# MCU.net
KiCad netlist of a schematic drawn in Altium Designer
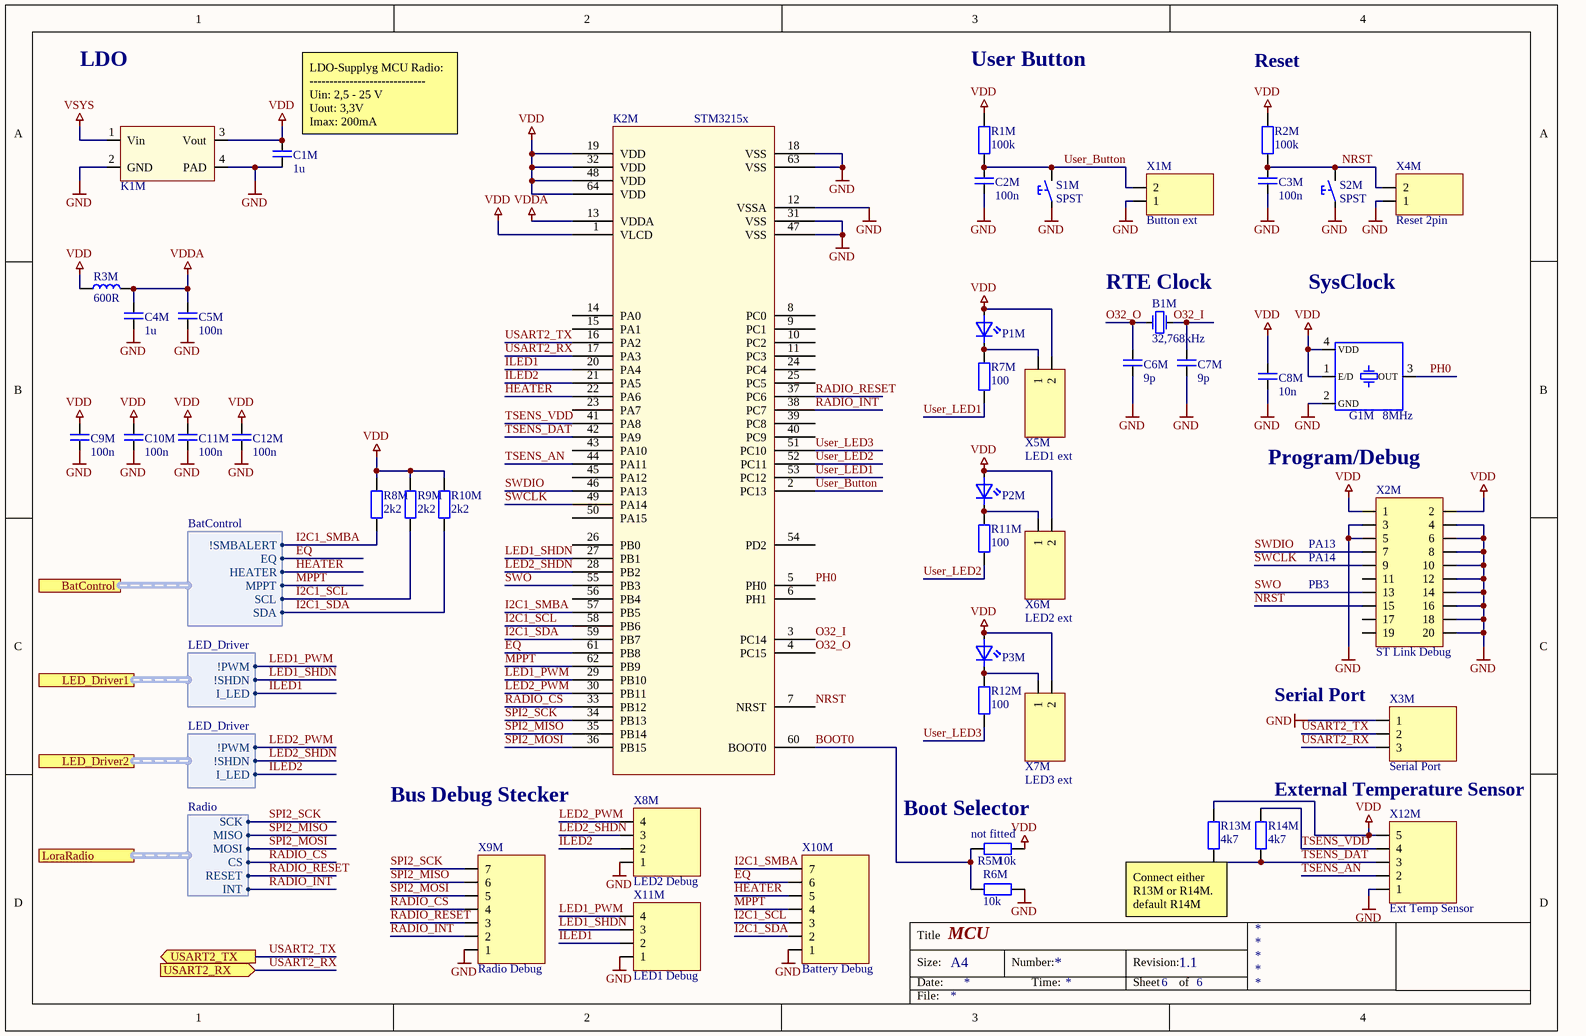
[diagram p0: MCU.SchDoc]

(export (version "E")
  (design (tool "Eeschema 10.0.6"))
  (components
    (comp (ref "B1M")
      (value "32,768kHz")
      (footprint "0805")
      (libsource (lib "Elektromechanical") (part "Quarz"))
    )
    (comp (ref "C1M") (value "1u") (footprint "0805") (libsource (lib "Passive") (part "Kondensator")))
    (comp (ref "C2M") (value "100n") (footprint "0805") (libsource (lib "Passive") (part "Kondensator")))
    (comp (ref "C3M") (value "100n") (footprint "0805") (libsource (lib "Passive") (part "Kondensator")))
    (comp (ref "C4M") (value "1u") (footprint "0805") (libsource (lib "Passive") (part "Kondensator")))
    (comp (ref "C5M") (value "100n") (footprint "0805") (libsource (lib "Passive") (part "Kondensator")))
    (comp (ref "C6M") (value "9p") (footprint "0805") (libsource (lib "Passive") (part "Kondensator")))
    (comp (ref "C7M") (value "9p") (footprint "0805") (libsource (lib "Passive") (part "Kondensator")))
    (comp (ref "C8M") (value "10n") (footprint "0805") (libsource (lib "Passive") (part "Kondensator")))
    (comp (ref "C9M") (value "100n") (footprint "0805") (libsource (lib "Passive") (part "Kondensator")))
    (comp (ref "C10M") (value "100n") (footprint "0805") (libsource (lib "Passive") (part "Kondensator")))
    (comp (ref "C11M") (value "100n") (footprint "0805") (libsource (lib "Passive") (part "Kondensator")))
    (comp (ref "C12M") (value "100n") (footprint "0805") (libsource (lib "Passive") (part "Kondensator")))
    (comp (ref "G1M")
      (value "8MHz")
      (footprint "SMT 3.2x2.5")
      (libsource (lib "Electromechanical") (part "Quarz Oszillator"))
    )
    (comp (ref "K1M") (value "LDO_2") (footprint "SOT223-4L") (libsource (lib "IC") (part "LDO_2")))
    (comp (ref "K2M")
      (value "STM3215x")
      (footprint "LQFP64, 0.5mm pitch")
      (libsource (lib "MCU") (part "STM32L15xRE_64"))
    )
    (comp (ref "P1M")
      (value "LED grün")
      (footprint "1206 D")
      (libsource (lib "Optoelectronics") (part "LED"))
    )
    (comp (ref "P2M")
      (value "LED gelb")
      (footprint "1206 D")
      (libsource (lib "Optoelectronics") (part "LED"))
    )
    (comp (ref "P3M") (value "LED rot") (footprint "1206 D") (libsource (lib "Optoelectronics") (part "LED")))
    (comp (ref "R1M") (value "100k") (footprint "0805") (libsource (lib "Passive") (part "Widerstand")))
    (comp (ref "R2M") (value "100k") (footprint "0805") (libsource (lib "Passive") (part "Widerstand")))
    (comp (ref "R3M")
      (value "600R")
      (footprint "0805")
      (description "EMI Filter")
      (libsource (lib "Passive") (part "Induktivität"))
    )
    (comp (ref "R5M") (value "10k") (footprint "0805") (libsource (lib "Passive") (part "Widerstand")))
    (comp (ref "R6M") (value "10k") (footprint "0805") (libsource (lib "Passive") (part "Widerstand")))
    (comp (ref "R7M") (value "100") (footprint "0805") (libsource (lib "Passive") (part "Widerstand")))
    (comp (ref "R8M") (value "2k2") (footprint "0805") (libsource (lib "Passive") (part "Widerstand")))
    (comp (ref "R9M") (value "2k2") (footprint "0805") (libsource (lib "Passive") (part "Widerstand")))
    (comp (ref "R10M") (value "2k2") (footprint "0805") (libsource (lib "Passive") (part "Widerstand")))
    (comp (ref "R11M") (value "100") (footprint "0805") (libsource (lib "Passive") (part "Widerstand")))
    (comp (ref "R12M") (value "100") (footprint "0805") (libsource (lib "Passive") (part "Widerstand")))
    (comp (ref "R13M") (value "4k7") (footprint "0805") (libsource (lib "Passive") (part "Widerstand")))
    (comp (ref "R14M") (value "4k7") (footprint "0805") (libsource (lib "Passive") (part "Widerstand")))
    (comp (ref "S1M")
      (value "SPST")
      (footprint "SPST_4x3")
      (description "single pole, single throw")
      (libsource (lib "Electromechanical") (part "SPST"))
    )
    (comp (ref "S2M")
      (value "SPST")
      (footprint "SPST_4x3")
      (description "single pole, single throw")
      (libsource (lib "Electromechanical") (part "SPST"))
    )
    (comp (ref "X1M")
      (value "Button ext")
      (footprint "Header, 2.54mm pitch, 2pin")
      (libsource (lib "") (part "Header 2pin_1"))
    )
    (comp (ref "X2M")
      (value "ST Link Debug")
      (footprint "Header, 2.54mm pitch, 2x10pin IDC socket male straight")
      (libsource (lib "Connectors") (part "Header 2x10pin"))
    )
    (comp (ref "X3M")
      (value "Serial Port")
      (footprint "Header, 2.54mm pitch, 3pin")
      (libsource (lib "Connectors") (part "Header 3pin"))
    )
    (comp (ref "X4M")
      (value "Reset 2pin")
      (footprint "Header, 2.54mm pitch, 2pin")
      (libsource (lib "") (part "Header 2pin_1"))
    )
    (comp (ref "X5M")
      (value "LED1 ext")
      (footprint "Header, 2.54mm pitch, 2pin")
      (libsource (lib "Connectors") (part "Header 2pin"))
    )
    (comp (ref "X6M")
      (value "LED2 ext")
      (footprint "Header, 2.54mm pitch, 2pin")
      (libsource (lib "Connectors") (part "Header 2pin"))
    )
    (comp (ref "X7M")
      (value "LED3 ext")
      (footprint "Header, 2.54mm pitch, 2pin")
      (libsource (lib "Connectors") (part "Header 2pin"))
    )
    (comp (ref "X8M")
      (value "LED2 Debug")
      (footprint "Header, 2.54mm pitch, 4pin")
      (libsource (lib "Connectors") (part "Header 4pin"))
    )
    (comp (ref "X9M")
      (value "Radio Debug")
      (footprint "Header, 2.54mm pitch, 7pin")
      (libsource (lib "Connectors") (part "Header 7pin"))
    )
    (comp (ref "X10M")
      (value "Battery Debug")
      (footprint "Header, 2.54mm pitch, 7pin")
      (libsource (lib "Connectors") (part "Header 7pin"))
    )
    (comp (ref "X11M")
      (value "LED1 Debug")
      (footprint "Header, 2.54mm pitch, 4pin")
      (libsource (lib "Connectors") (part "Header 4pin"))
    )
    (comp (ref "X12M")
      (value "Ext Temp Sensor")
      (footprint "Header, 2.54mm pitch, 5pin")
      (libsource (lib "Connectors") (part "Header 5pin"))
    )
  )
  (nets
    (net (code "4") (name "/BOOT0") (class "Default")
      (node (ref "K2M") (pin "60") (pinfunction "BOOT0_60") (pintype "passive"))
      (node (ref "R5M") (pin "1") (pinfunction "1_1") (pintype "passive"))
      (node (ref "R6M") (pin "1") (pinfunction "1_1") (pintype "passive"))
    )
    (net (code "5") (name "/EQ") (class "Default")
      (node (ref "K2M") (pin "61") (pinfunction "PB8_61") (pintype "passive"))
      (node (ref "X10M") (pin "6") (pinfunction "6_6") (pintype "passive"))
    )
    (net (code "6") (name "/HEATER") (class "Default")
      (node (ref "K2M") (pin "22") (pinfunction "PA6_22") (pintype "passive"))
      (node (ref "X10M") (pin "5") (pinfunction "5_5") (pintype "passive"))
    )
    (net (code "7") (name "/I2C1_SCL") (class "Default")
      (node (ref "K2M") (pin "58") (pinfunction "PB6_58") (pintype "passive"))
      (node (ref "R9M") (pin "1") (pinfunction "1_1") (pintype "passive"))
      (node (ref "X10M") (pin "3") (pinfunction "3_3") (pintype "passive"))
    )
    (net (code "8") (name "/I2C1_SDA") (class "Default")
      (node (ref "K2M") (pin "59") (pinfunction "PB7_59") (pintype "passive"))
      (node (ref "R10M") (pin "1") (pinfunction "1_1") (pintype "passive"))
      (node (ref "X10M") (pin "2") (pinfunction "2_2") (pintype "passive"))
    )
    (net (code "9") (name "/I2C1_SMBA") (class "Default")
      (node (ref "K2M") (pin "57") (pinfunction "PB5_57") (pintype "passive"))
      (node (ref "R8M") (pin "1") (pinfunction "1_1") (pintype "passive"))
      (node (ref "X10M") (pin "7") (pinfunction "7_7") (pintype "passive"))
    )
    (net (code "10") (name "/ILED1") (class "Default")
      (node (ref "K2M") (pin "20") (pinfunction "PA4_20") (pintype "passive"))
      (node (ref "X11M") (pin "2") (pinfunction "2_2") (pintype "passive"))
    )
    (net (code "11") (name "/ILED2") (class "Default")
      (node (ref "K2M") (pin "21") (pinfunction "PA5_21") (pintype "passive"))
      (node (ref "X8M") (pin "2") (pinfunction "2_2") (pintype "passive"))
    )
    (net (code "12") (name "/LED1_PWM") (class "Default")
      (node (ref "K2M") (pin "29") (pinfunction "PB10_29") (pintype "passive"))
      (node (ref "X11M") (pin "4") (pinfunction "4_4") (pintype "passive"))
    )
    (net (code "13") (name "/LED1_SHDN") (class "Default")
      (node (ref "K2M") (pin "27") (pinfunction "PB1_27") (pintype "passive"))
      (node (ref "X11M") (pin "3") (pinfunction "3_3") (pintype "passive"))
    )
    (net (code "14") (name "/LED2_PWM") (class "Default")
      (node (ref "K2M") (pin "30") (pinfunction "PB11_30") (pintype "passive"))
      (node (ref "X8M") (pin "4") (pinfunction "4_4") (pintype "passive"))
    )
    (net (code "15") (name "/LED2_SHDN") (class "Default")
      (node (ref "K2M") (pin "28") (pinfunction "PB2_28") (pintype "passive"))
      (node (ref "X8M") (pin "3") (pinfunction "3_3") (pintype "passive"))
    )
    (net (code "16") (name "/MPPT") (class "Default")
      (node (ref "K2M") (pin "62") (pinfunction "PB9_62") (pintype "passive"))
      (node (ref "X10M") (pin "4") (pinfunction "4_4") (pintype "passive"))
    )
    (net (code "17") (name "/NRST") (class "Default")
      (node (ref "C3M") (pin "2") (pinfunction "2_2") (pintype "passive"))
      (node (ref "K2M") (pin "7") (pinfunction "NRST_7") (pintype "passive"))
      (node (ref "R2M") (pin "1") (pinfunction "1_1") (pintype "passive"))
      (node (ref "S2M") (pin "2") (pinfunction "Schließer_2") (pintype "passive"))
      (node (ref "X2M") (pin "15") (pinfunction "15_15") (pintype "passive"))
      (node (ref "X4M") (pin "2") (pinfunction "2_2") (pintype "passive"))
    )
    (net (code "18") (name "/O32_I") (class "Default")
      (node (ref "B1M") (pin "2") (pintype "passive"))
      (node (ref "C7M") (pin "2") (pinfunction "2_2") (pintype "passive"))
      (node (ref "K2M") (pin "3") (pinfunction "PC14_3") (pintype "passive"))
    )
    (net (code "19") (name "/O32_O") (class "Default")
      (node (ref "B1M") (pin "1") (pintype "passive"))
      (node (ref "C6M") (pin "2") (pinfunction "2_2") (pintype "passive"))
      (node (ref "K2M") (pin "4") (pinfunction "PC15_4") (pintype "passive"))
    )
    (net (code "20") (name "/PH0") (class "Default")
      (node (ref "G1M") (pin "3") (pinfunction "OUT_3") (pintype "passive"))
      (node (ref "K2M") (pin "5") (pinfunction "PH0_5") (pintype "passive"))
    )
    (net (code "21") (name "/RADIO_CS") (class "Default")
      (node (ref "K2M") (pin "33") (pinfunction "PB12_33") (pintype "passive"))
      (node (ref "X9M") (pin "4") (pinfunction "4_4") (pintype "passive"))
    )
    (net (code "22") (name "/RADIO_INT") (class "Default")
      (node (ref "K2M") (pin "38") (pinfunction "PC7_38") (pintype "passive"))
      (node (ref "X9M") (pin "2") (pinfunction "2_2") (pintype "passive"))
    )
    (net (code "23") (name "/RADIO_RESET") (class "Default")
      (node (ref "K2M") (pin "37") (pinfunction "PC6_37") (pintype "passive"))
      (node (ref "X9M") (pin "3") (pinfunction "3_3") (pintype "passive"))
    )
    (net (code "24") (name "/SPI2_MISO") (class "Default")
      (node (ref "K2M") (pin "35") (pinfunction "PB14_35") (pintype "passive"))
      (node (ref "X9M") (pin "6") (pinfunction "6_6") (pintype "passive"))
    )
    (net (code "25") (name "/SPI2_MOSI") (class "Default")
      (node (ref "K2M") (pin "36") (pinfunction "PB15_36") (pintype "passive"))
      (node (ref "X9M") (pin "5") (pinfunction "5_5") (pintype "passive"))
    )
    (net (code "26") (name "/SPI2_SCK") (class "Default")
      (node (ref "K2M") (pin "34") (pinfunction "PB13_34") (pintype "passive"))
      (node (ref "X9M") (pin "7") (pinfunction "7_7") (pintype "passive"))
    )
    (net (code "27") (name "/SWCLK") (class "Default")
      (node (ref "K2M") (pin "49") (pinfunction "PA14_49") (pintype "passive"))
      (node (ref "X2M") (pin "9") (pinfunction "9_9") (pintype "passive"))
    )
    (net (code "28") (name "/SWDIO") (class "Default")
      (node (ref "K2M") (pin "46") (pinfunction "PA13_46") (pintype "passive"))
      (node (ref "X2M") (pin "7") (pinfunction "7_7") (pintype "passive"))
    )
    (net (code "29") (name "/SWO") (class "Default")
      (node (ref "K2M") (pin "55") (pinfunction "PB3_55") (pintype "passive"))
      (node (ref "X2M") (pin "13") (pinfunction "13_13") (pintype "passive"))
    )
    (net (code "30") (name "/TSENS_AN") (class "Default")
      (node (ref "K2M") (pin "44") (pinfunction "PA11_44") (pintype "passive"))
      (node (ref "X12M") (pin "2") (pinfunction "2_2") (pintype "passive"))
    )
    (net (code "31") (name "/TSENS_DAT") (class "Default")
      (node (ref "K2M") (pin "42") (pinfunction "PA9_42") (pintype "passive"))
      (node (ref "R13M") (pin "1") (pinfunction "1_1") (pintype "passive"))
      (node (ref "R14M") (pin "1") (pinfunction "1_1") (pintype "passive"))
      (node (ref "X12M") (pin "3") (pinfunction "3_3") (pintype "passive"))
    )
    (net (code "32") (name "/TSENS_VDD") (class "Default")
      (node (ref "K2M") (pin "41") (pinfunction "PA8_41") (pintype "passive"))
      (node (ref "R14M") (pin "2") (pinfunction "2_2") (pintype "passive"))
      (node (ref "X12M") (pin "4") (pinfunction "4_4") (pintype "passive"))
    )
    (net (code "33") (name "/USART2_RX") (class "Default")
      (node (ref "K2M") (pin "17") (pinfunction "PA3_17") (pintype "passive"))
      (node (ref "X3M") (pin "3") (pinfunction "3_3") (pintype "passive"))
    )
    (net (code "34") (name "/USART2_TX") (class "Default")
      (node (ref "K2M") (pin "16") (pinfunction "PA2_16") (pintype "passive"))
      (node (ref "X3M") (pin "2") (pinfunction "2_2") (pintype "passive"))
    )
    (net (code "35") (name "/User_Button") (class "Default")
      (node (ref "C2M") (pin "2") (pinfunction "2_2") (pintype "passive"))
      (node (ref "K2M") (pin "2") (pinfunction "PC13_2") (pintype "passive"))
      (node (ref "R1M") (pin "1") (pinfunction "1_1") (pintype "passive"))
      (node (ref "S1M") (pin "2") (pinfunction "Schließer_2") (pintype "passive"))
      (node (ref "X1M") (pin "2") (pinfunction "2_2") (pintype "passive"))
    )
    (net (code "36") (name "/User_LED1") (class "Default")
      (node (ref "K2M") (pin "53") (pinfunction "PC12_53") (pintype "passive"))
      (node (ref "R7M") (pin "1") (pinfunction "1_1") (pintype "passive"))
    )
    (net (code "37") (name "/User_LED2") (class "Default")
      (node (ref "K2M") (pin "52") (pinfunction "PC11_52") (pintype "passive"))
      (node (ref "R11M") (pin "1") (pinfunction "1_1") (pintype "passive"))
    )
    (net (code "38") (name "/User_LED3") (class "Default")
      (node (ref "K2M") (pin "51") (pinfunction "PC10_51") (pintype "passive"))
      (node (ref "R12M") (pin "1") (pinfunction "1_1") (pintype "passive"))
    )
    (net (code "42") (name "GND") (class "Default")
      (node (ref "C10M") (pin "1") (pinfunction "1_1") (pintype "passive"))
      (node (ref "C11M") (pin "1") (pinfunction "1_1") (pintype "passive"))
      (node (ref "C12M") (pin "1") (pinfunction "1_1") (pintype "passive"))
      (node (ref "C1M") (pin "1") (pinfunction "1_1") (pintype "passive"))
      (node (ref "C2M") (pin "1") (pinfunction "1_1") (pintype "passive"))
      (node (ref "C3M") (pin "1") (pinfunction "1_1") (pintype "passive"))
      (node (ref "C4M") (pin "1") (pinfunction "1_1") (pintype "passive"))
      (node (ref "C5M") (pin "1") (pinfunction "1_1") (pintype "passive"))
      (node (ref "C6M") (pin "1") (pinfunction "1_1") (pintype "passive"))
      (node (ref "C7M") (pin "1") (pinfunction "1_1") (pintype "passive"))
      (node (ref "C8M") (pin "1") (pinfunction "1_1") (pintype "passive"))
      (node (ref "C9M") (pin "1") (pinfunction "1_1") (pintype "passive"))
      (node (ref "G1M") (pin "2") (pinfunction "GND_2") (pintype "passive"))
      (node (ref "K1M") (pin "2") (pinfunction "GND_2") (pintype "passive"))
      (node (ref "K1M") (pin "4") (pinfunction "PAD_4") (pintype "passive"))
      (node (ref "K2M") (pin "12") (pinfunction "VSSA_12") (pintype "passive"))
      (node (ref "K2M") (pin "18") (pinfunction "VSS_18") (pintype "passive"))
      (node (ref "K2M") (pin "31") (pinfunction "VSS_31") (pintype "passive"))
      (node (ref "K2M") (pin "47") (pinfunction "VSS_47") (pintype "passive"))
      (node (ref "K2M") (pin "63") (pinfunction "VSS_63") (pintype "passive"))
      (node (ref "R6M") (pin "2") (pinfunction "2_2") (pintype "passive"))
      (node (ref "S1M") (pin "1") (pinfunction "Mitte_1") (pintype "passive"))
      (node (ref "S2M") (pin "1") (pinfunction "Mitte_1") (pintype "passive"))
      (node (ref "X10M") (pin "1") (pinfunction "1_1") (pintype "passive"))
      (node (ref "X11M") (pin "1") (pinfunction "1_1") (pintype "passive"))
      (node (ref "X12M") (pin "1") (pinfunction "1_1") (pintype "passive"))
      (node (ref "X1M") (pin "1") (pinfunction "1_1") (pintype "passive"))
      (node (ref "X2M") (pin "10") (pinfunction "10_10") (pintype "passive"))
      (node (ref "X2M") (pin "12") (pinfunction "12_12") (pintype "passive"))
      (node (ref "X2M") (pin "14") (pinfunction "14_14") (pintype "passive"))
      (node (ref "X2M") (pin "16") (pinfunction "16_16") (pintype "passive"))
      (node (ref "X2M") (pin "18") (pinfunction "18_18") (pintype "passive"))
      (node (ref "X2M") (pin "20") (pinfunction "20_20") (pintype "passive"))
      (node (ref "X2M") (pin "3") (pinfunction "3_3") (pintype "passive"))
      (node (ref "X2M") (pin "4") (pinfunction "4_4") (pintype "passive"))
      (node (ref "X2M") (pin "5") (pinfunction "5_5") (pintype "passive"))
      (node (ref "X2M") (pin "6") (pinfunction "6_6") (pintype "passive"))
      (node (ref "X2M") (pin "8") (pinfunction "8_8") (pintype "passive"))
      (node (ref "X3M") (pin "1") (pinfunction "1_1") (pintype "passive"))
      (node (ref "X4M") (pin "1") (pinfunction "1_1") (pintype "passive"))
      (node (ref "X8M") (pin "1") (pinfunction "1_1") (pintype "passive"))
      (node (ref "X9M") (pin "1") (pinfunction "1_1") (pintype "passive"))
    )
    (net (code "43") (name "Net-(P1M-Kathode)") (class "Default")
      (node (ref "P1M") (pin "1") (pinfunction "Kathode_1") (pintype "passive"))
      (node (ref "R7M") (pin "2") (pinfunction "2_2") (pintype "passive"))
      (node (ref "X5M") (pin "1") (pinfunction "1_1") (pintype "passive"))
    )
    (net (code "44") (name "Net-(P2M-Kathode)") (class "Default")
      (node (ref "P2M") (pin "1") (pinfunction "Kathode_1") (pintype "passive"))
      (node (ref "R11M") (pin "2") (pinfunction "2_2") (pintype "passive"))
      (node (ref "X6M") (pin "1") (pinfunction "1_1") (pintype "passive"))
    )
    (net (code "45") (name "Net-(P3M-Kathode)") (class "Default")
      (node (ref "P3M") (pin "1") (pinfunction "Kathode_1") (pintype "passive"))
      (node (ref "R12M") (pin "2") (pinfunction "2_2") (pintype "passive"))
      (node (ref "X7M") (pin "1") (pinfunction "1_1") (pintype "passive"))
    )
    (net (code "46") (name "VDD") (class "Default")
      (node (ref "C10M") (pin "2") (pinfunction "2_2") (pintype "passive"))
      (node (ref "C11M") (pin "2") (pinfunction "2_2") (pintype "passive"))
      (node (ref "C12M") (pin "2") (pinfunction "2_2") (pintype "passive"))
      (node (ref "C1M") (pin "2") (pinfunction "2_2") (pintype "passive"))
      (node (ref "C8M") (pin "2") (pinfunction "2_2") (pintype "passive"))
      (node (ref "C9M") (pin "2") (pinfunction "2_2") (pintype "passive"))
      (node (ref "G1M") (pin "1") (pinfunction "E/D_1") (pintype "passive"))
      (node (ref "G1M") (pin "4") (pinfunction "VDD_4") (pintype "passive"))
      (node (ref "K1M") (pin "3") (pinfunction "Vout_3") (pintype "power_in"))
      (node (ref "K2M") (pin "1") (pinfunction "VLCD_1") (pintype "passive"))
      (node (ref "K2M") (pin "19") (pinfunction "VDD_19") (pintype "passive"))
      (node (ref "K2M") (pin "32") (pinfunction "VDD_32") (pintype "passive"))
      (node (ref "K2M") (pin "48") (pinfunction "VDD_48") (pintype "passive"))
      (node (ref "K2M") (pin "64") (pinfunction "VDD_64") (pintype "passive"))
      (node (ref "P1M") (pin "2") (pinfunction "Annode_2") (pintype "passive"))
      (node (ref "P2M") (pin "2") (pinfunction "Annode_2") (pintype "passive"))
      (node (ref "P3M") (pin "2") (pinfunction "Annode_2") (pintype "passive"))
      (node (ref "R10M") (pin "2") (pinfunction "2_2") (pintype "passive"))
      (node (ref "R13M") (pin "2") (pinfunction "2_2") (pintype "passive"))
      (node (ref "R1M") (pin "2") (pinfunction "2_2") (pintype "passive"))
      (node (ref "R2M") (pin "2") (pinfunction "2_2") (pintype "passive"))
      (node (ref "R3M") (pin "1") (pinfunction "1_1") (pintype "passive"))
      (node (ref "R5M") (pin "2") (pinfunction "2_2") (pintype "passive"))
      (node (ref "R8M") (pin "2") (pinfunction "2_2") (pintype "passive"))
      (node (ref "R9M") (pin "2") (pinfunction "2_2") (pintype "passive"))
      (node (ref "X12M") (pin "5") (pinfunction "5_5") (pintype "passive"))
      (node (ref "X2M") (pin "1") (pinfunction "1_1") (pintype "passive"))
      (node (ref "X2M") (pin "2") (pinfunction "2_2") (pintype "passive"))
      (node (ref "X5M") (pin "2") (pinfunction "2_2") (pintype "passive"))
      (node (ref "X6M") (pin "2") (pinfunction "2_2") (pintype "passive"))
      (node (ref "X7M") (pin "2") (pinfunction "2_2") (pintype "passive"))
    )
    (net (code "47") (name "VDDA") (class "Default")
      (node (ref "C4M") (pin "2") (pinfunction "2_2") (pintype "passive"))
      (node (ref "C5M") (pin "2") (pinfunction "2_2") (pintype "passive"))
      (node (ref "K2M") (pin "13") (pinfunction "VDDA_13") (pintype "passive"))
      (node (ref "R3M") (pin "2") (pinfunction "2_2") (pintype "passive"))
    )
    (net (code "48") (name "VSYS") (class "Default")
      (node (ref "K1M") (pin "1") (pinfunction "Vin_1") (pintype "power_in"))
    )
    (net (code "49") (name "unconnected-(K2M-PA0-Pad14)") (class "Default")
      (node (ref "K2M") (pin "14") (pinfunction "PA0_14") (pintype "passive"))
    )
    (net (code "50") (name "unconnected-(K2M-PA1-Pad15)") (class "Default")
      (node (ref "K2M") (pin "15") (pinfunction "PA1_15") (pintype "passive"))
    )
    (net (code "51") (name "unconnected-(K2M-PA7-Pad23)") (class "Default")
      (node (ref "K2M") (pin "23") (pinfunction "PA7_23") (pintype "passive"))
    )
    (net (code "52") (name "unconnected-(K2M-PA10-Pad43)") (class "Default")
      (node (ref "K2M") (pin "43") (pinfunction "PA10_43") (pintype "passive"))
    )
    (net (code "53") (name "unconnected-(K2M-PA12-Pad45)") (class "Default")
      (node (ref "K2M") (pin "45") (pinfunction "PA12_45") (pintype "passive"))
    )
    (net (code "54") (name "unconnected-(K2M-PA15-Pad50)") (class "Default")
      (node (ref "K2M") (pin "50") (pinfunction "PA15_50") (pintype "passive"))
    )
    (net (code "55") (name "unconnected-(K2M-PB0-Pad26)") (class "Default")
      (node (ref "K2M") (pin "26") (pinfunction "PB0_26") (pintype "passive"))
    )
    (net (code "56") (name "unconnected-(K2M-PB4-Pad56)") (class "Default")
      (node (ref "K2M") (pin "56") (pinfunction "PB4_56") (pintype "passive"))
    )
    (net (code "57") (name "unconnected-(K2M-PC0-Pad8)") (class "Default")
      (node (ref "K2M") (pin "8") (pinfunction "PC0_8") (pintype "passive"))
    )
    (net (code "58") (name "unconnected-(K2M-PC1-Pad9)") (class "Default")
      (node (ref "K2M") (pin "9") (pinfunction "PC1_9") (pintype "passive"))
    )
    (net (code "59") (name "unconnected-(K2M-PC2-Pad10)") (class "Default")
      (node (ref "K2M") (pin "10") (pinfunction "PC2_10") (pintype "passive"))
    )
    (net (code "60") (name "unconnected-(K2M-PC3-Pad11)") (class "Default")
      (node (ref "K2M") (pin "11") (pinfunction "PC3_11") (pintype "passive"))
    )
    (net (code "61") (name "unconnected-(K2M-PC4-Pad24)") (class "Default")
      (node (ref "K2M") (pin "24") (pinfunction "PC4_24") (pintype "passive"))
    )
    (net (code "62") (name "unconnected-(K2M-PC5-Pad25)") (class "Default")
      (node (ref "K2M") (pin "25") (pinfunction "PC5_25") (pintype "passive"))
    )
    (net (code "63") (name "unconnected-(K2M-PC8-Pad39)") (class "Default")
      (node (ref "K2M") (pin "39") (pinfunction "PC8_39") (pintype "passive"))
    )
    (net (code "64") (name "unconnected-(K2M-PC9-Pad40)") (class "Default")
      (node (ref "K2M") (pin "40") (pinfunction "PC9_40") (pintype "passive"))
    )
    (net (code "65") (name "unconnected-(K2M-PD2-Pad54)") (class "Default")
      (node (ref "K2M") (pin "54") (pinfunction "PD2_54") (pintype "passive"))
    )
    (net (code "66") (name "unconnected-(K2M-PH1-Pad6)") (class "Default")
      (node (ref "K2M") (pin "6") (pinfunction "PH1_6") (pintype "passive"))
    )
    (net (code "67") (name "unconnected-(X2M-Pad11)") (class "Default")
      (node (ref "X2M") (pin "11") (pinfunction "11_11") (pintype "passive"))
    )
    (net (code "68") (name "unconnected-(X2M-Pad17)") (class "Default")
      (node (ref "X2M") (pin "17") (pinfunction "17_17") (pintype "passive"))
    )
    (net (code "69") (name "unconnected-(X2M-Pad19)") (class "Default")
      (node (ref "X2M") (pin "19") (pinfunction "19_19") (pintype "passive"))
    )
  )
)
